# LM2587.net
KiCad netlist of a schematic drawn in Altium Designer
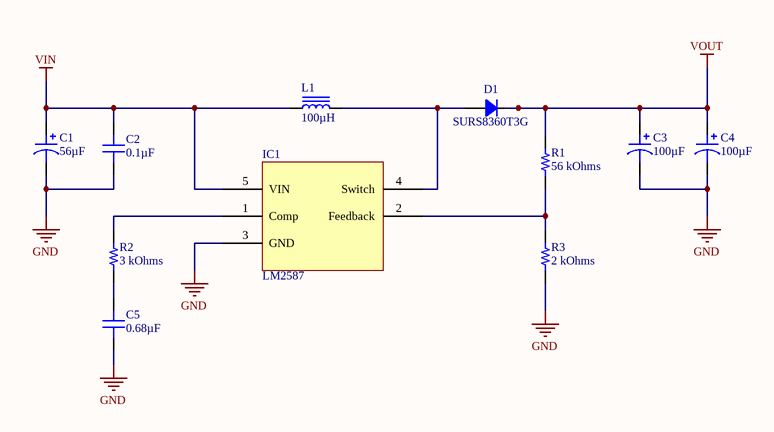
[diagram p0: LM2587.SchDoc]

(export (version "E")
  (design (tool "Eeschema 10.0.6"))
  (components
    (comp (ref "C1")
      (value "56µF")
      (footprint "CAP ALSMD 6.6MM H7.7MM")
      (description "CAP ALUM 56UF 20% 35V SMD")
      (fields (field (name "PART NUMBER") "UUD1V560MCL1GS") (field (name "MANUFACTURER") "Nichicon"))
      (libsource (lib "Celestial Altium Library - altium_library") (part "Polarised Capacitor"))
    )
    (comp (ref "C2")
      (value "0.1µF")
      (footprint "CAP 0805_2012")
      (description "CAP CER 0.1UF 50V X7R 0805")
      (fields (field (name "PART NUMBER") "VJ0805Y104MXAMR") (field (name "MANUFACTURER") "Vishay Vitramon"))
      (libsource (lib "Celestial Altium Library - altium_library") (part "Capacitor"))
    )
    (comp (ref "C3")
      (value "100µF")
      (footprint "CAP ALSMD 8.3MM H10.5MM")
      (description "CAP ALUM 100UF 20% 50V SMD")
      (fields
        (field (name "PART NUMBER") "EEE-FK1H101P")
        (field (name "MANUFACTURER") "Panasonic Electronic Components")
      )
      (libsource (lib "Celestial Altium Library - altium_library") (part "Polarised Capacitor"))
    )
    (comp (ref "C4")
      (value "100µF")
      (footprint "CAP ALSMD 8.3MM H10.5MM")
      (description "CAP ALUM 100UF 20% 50V SMD")
      (fields
        (field (name "PART NUMBER") "EEE-FK1H101P")
        (field (name "MANUFACTURER") "Panasonic Electronic Components")
      )
      (libsource (lib "Celestial Altium Library - altium_library") (part "Polarised Capacitor"))
    )
    (comp (ref "C5")
      (value "0.68µF")
      (footprint "CAP 0805_2012")
      (description "CAP CER 0.68UF 50V X7R 0805")
      (fields (field (name "PART NUMBER") "C0805X684K5RECAUTO") (field (name "MANUFACTURER") "KEMET"))
      (libsource (lib "Celestial Altium Library - altium_library") (part "Capacitor"))
    )
    (comp (ref "D1")
      (value "SURS8360T3G")
      (footprint "DO214AB SMC")
      (description "DIODE GEN PURP 600V 3A SMC")
      (fields (field (name "MANUFACTURER") "ON Semiconductor"))
      (libsource (lib "Celestial Altium Library - altium_library") (part "Diode"))
    )
    (comp (ref "IC1")
      (value "LM2587")
      (footprint "D2PAK")
      (description "Boost Converter")
      (libsource (lib "BoostConverter_Library") (part "LM2587"))
    )
    (comp (ref "L1")
      (value "100µH")
      (footprint "BoostConverter_Library:7447070")
      (description "FIXED IND 100UH 2.1A 150MOHM SMD")
      (fields (field (name "PART NUMBER") "SRR1280-101M") (field (name "MANUFACTURER") "Bourns Inc."))
      (libsource (lib "Celestial Altium Library - altium_library") (part "Inductor"))
    )
    (comp (ref "R1")
      (value "56 kOhms")
      (footprint "RES 0805_2012")
      (description "RES SMD 56K OHM 1% 1/8W 0805")
      (fields (field (name "PART NUMBER") "CRCW080556K0FKEA") (field (name "MANUFACTURER") "Vishay Dale"))
      (libsource (lib "Celestial Altium Library - altium_library") (part "Resistor"))
    )
    (comp (ref "R2")
      (value "3 kOhms")
      (footprint "RES 0805_2012")
      (description "RES SMD 3K OHM 1% 1/8W 0805")
      (fields
        (field (name "PART NUMBER") "ERJ-6ENF3001V")
        (field (name "MANUFACTURER") "Panasonic Electronic Components")
      )
      (libsource (lib "Celestial Altium Library - altium_library") (part "Resistor"))
    )
    (comp (ref "R3")
      (value "2 kOhms")
      (footprint "RES 0805_2012")
      (description "RES SMD 2K OHM 1% 1/8W 0805")
      (fields (field (name "PART NUMBER") "RC0805FR-072KP") (field (name "MANUFACTURER") "Yageo"))
      (libsource (lib "Celestial Altium Library - altium_library") (part "Resistor"))
    )
  )
  (nets
    (net (code "1") (name "GND") (class "Default")
      (node (ref "C1") (pin "2") (pinfunction "2_2") (pintype "passive"))
      (node (ref "C2") (pin "1") (pinfunction "1_1") (pintype "passive"))
      (node (ref "C3") (pin "2") (pinfunction "2_2") (pintype "passive"))
      (node (ref "C4") (pin "2") (pinfunction "2_2") (pintype "passive"))
      (node (ref "C5") (pin "1") (pinfunction "1_1") (pintype "passive"))
      (node (ref "IC1") (pin "3") (pinfunction "GND_3") (pintype "passive"))
      (node (ref "R3") (pin "1") (pinfunction "1_1") (pintype "passive"))
    )
    (net (code "2") (name "Net-(C5-Pad2)") (class "Default")
      (node (ref "C5") (pin "2") (pinfunction "2_2") (pintype "passive"))
      (node (ref "R2") (pin "1") (pinfunction "1_1") (pintype "passive"))
    )
    (net (code "3") (name "Net-(IC1-Comp)") (class "Default")
      (node (ref "IC1") (pin "1") (pinfunction "Comp_1") (pintype "passive"))
      (node (ref "R2") (pin "2") (pinfunction "2_2") (pintype "passive"))
    )
    (net (code "4") (name "Net-(IC1-Feedback)") (class "Default")
      (node (ref "IC1") (pin "2") (pinfunction "Feedback_2") (pintype "passive"))
      (node (ref "R1") (pin "1") (pinfunction "1_1") (pintype "passive"))
      (node (ref "R3") (pin "2") (pinfunction "2_2") (pintype "passive"))
    )
    (net (code "5") (name "Net-(IC1-Switch)") (class "Default")
      (node (ref "D1") (pin "1") (pinfunction "1_1") (pintype "passive"))
      (node (ref "IC1") (pin "4") (pinfunction "Switch_4") (pintype "passive"))
      (node (ref "L1") (pin "2") (pinfunction "2_2") (pintype "passive"))
    )
    (net (code "6") (name "VIN") (class "Default")
      (node (ref "C1") (pin "1") (pinfunction "1_1") (pintype "passive"))
      (node (ref "C2") (pin "2") (pinfunction "2_2") (pintype "passive"))
      (node (ref "IC1") (pin "5") (pinfunction "VIN_5") (pintype "passive"))
      (node (ref "L1") (pin "1") (pinfunction "1_1") (pintype "passive"))
    )
    (net (code "7") (name "VOUT") (class "Default")
      (node (ref "C3") (pin "1") (pinfunction "1_1") (pintype "passive"))
      (node (ref "C4") (pin "1") (pinfunction "1_1") (pintype "passive"))
      (node (ref "D1") (pin "2") (pinfunction "2_2") (pintype "passive"))
      (node (ref "R1") (pin "2") (pinfunction "2_2") (pintype "passive"))
    )
  )
)
